# Photodiodeboard.net
KiCad netlist of a schematic drawn in Altium Designer
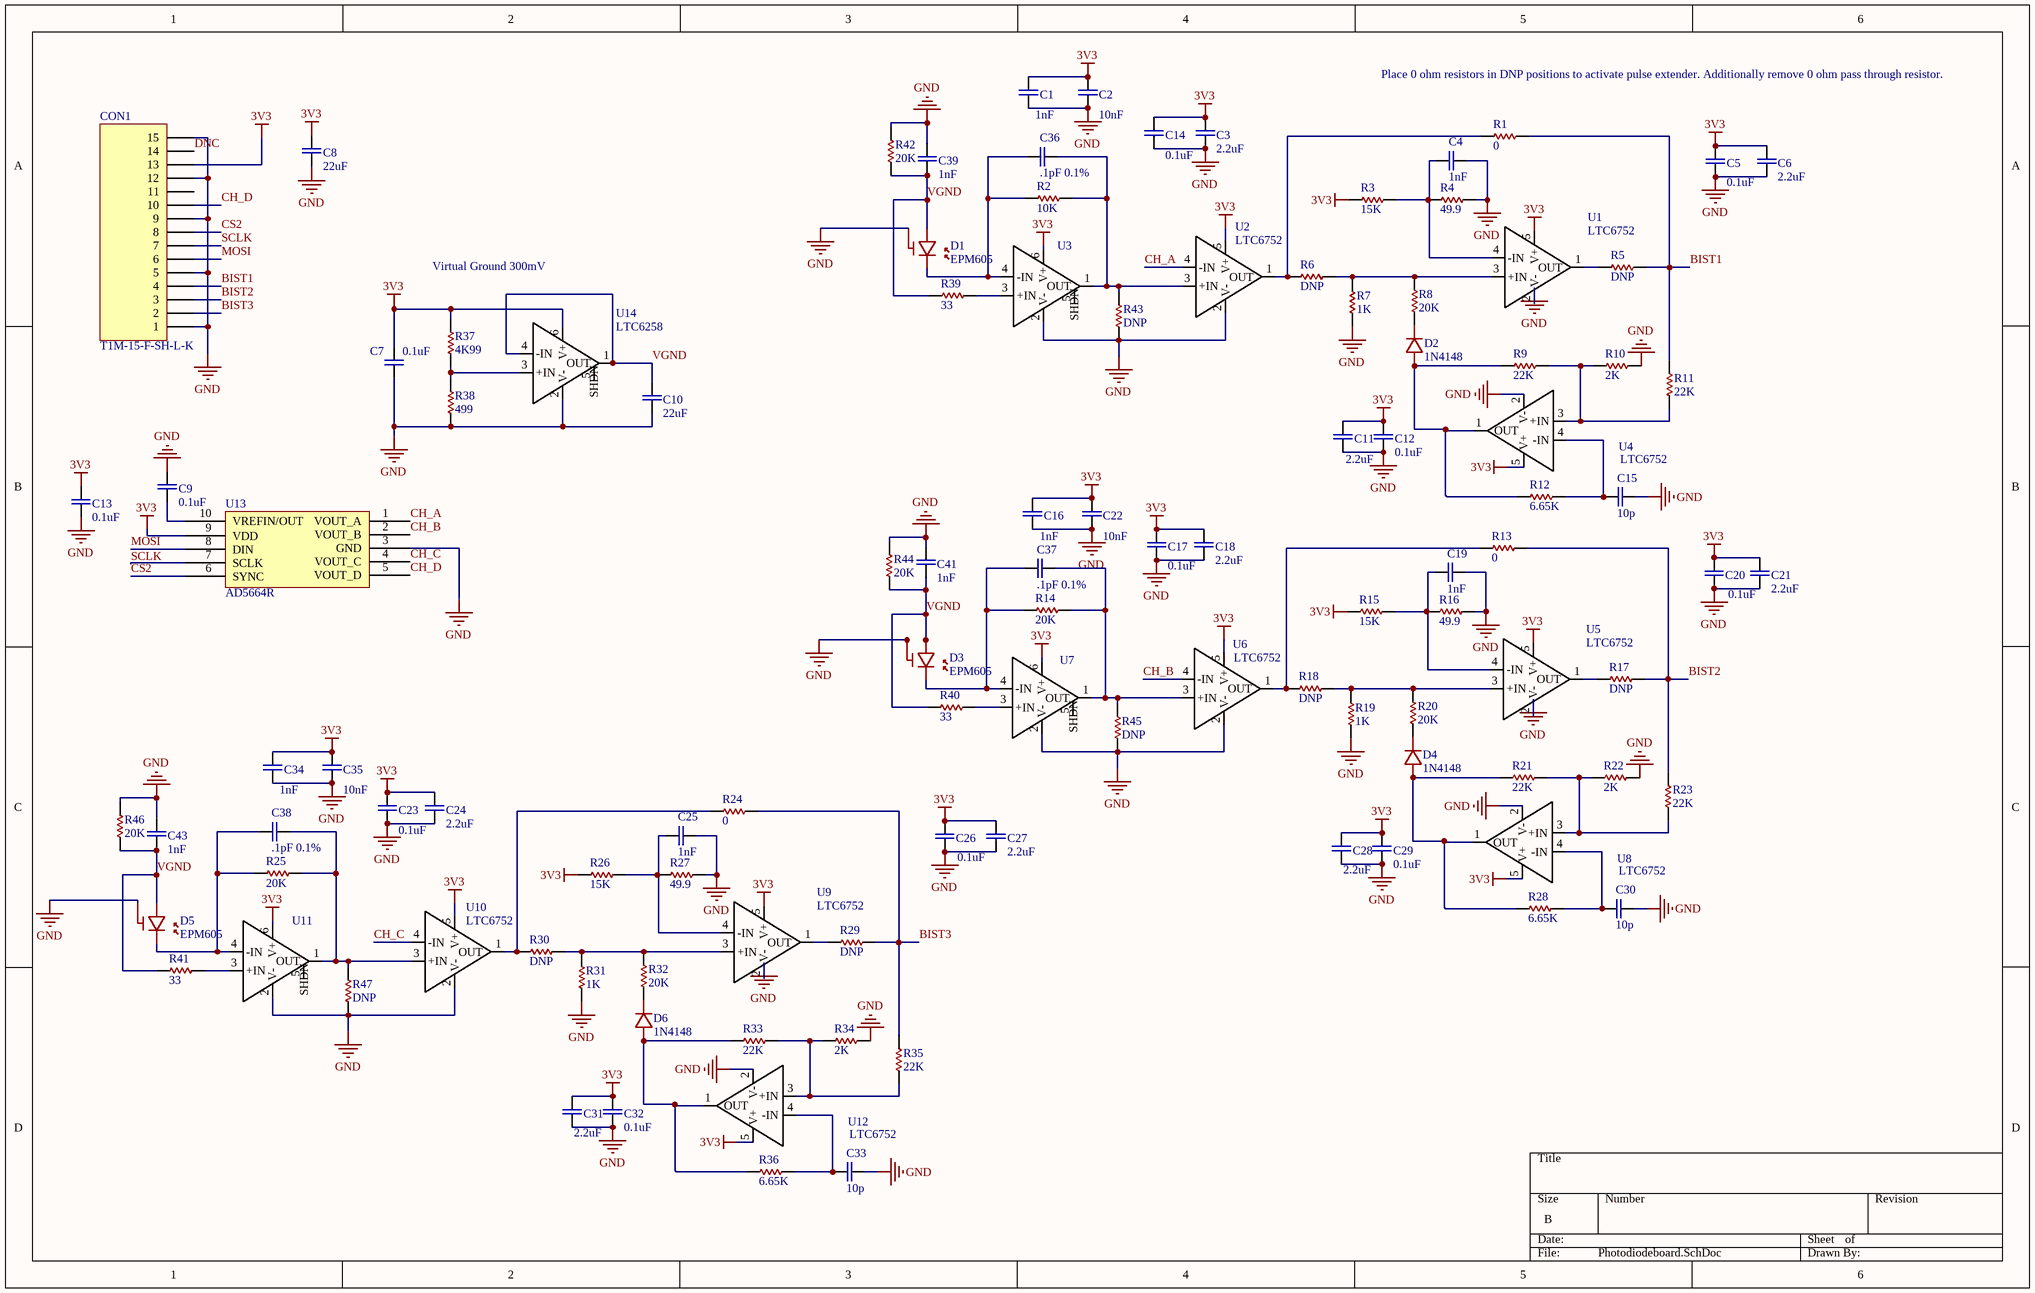
[diagram p0: Photodiodeboard.SchDoc]

(export (version "E")
  (design (tool "Eeschema 10.0.6"))
  (components
    (comp (ref "C1") (value "1nF") (footprint "0402") (libsource (lib "SchLib819") (part "Cap 0402")))
    (comp (ref "C2") (value "10nF") (footprint "0402") (libsource (lib "SchLib819") (part "Cap 0402")))
    (comp (ref "C3") (value "2.2uF") (footprint "0402") (libsource (lib "SchLib819") (part "Cap 0402")))
    (comp (ref "C4") (value "1nF") (footprint "0402") (libsource (lib "SchLib819") (part "Cap 0402")))
    (comp (ref "C5") (value "0.1uF") (footprint "0402") (libsource (lib "SchLib819") (part "Cap 0402")))
    (comp (ref "C6") (value "2.2uF") (footprint "0402") (libsource (lib "SchLib819") (part "Cap 0402")))
    (comp (ref "C7") (value "0.1uF") (footprint "0402") (libsource (lib "SchLib819") (part "Cap 0402")))
    (comp (ref "C8") (value "22uF") (footprint "0603") (libsource (lib "SchLib819") (part "Cap 0603")))
    (comp (ref "C9") (value "0.1uF") (footprint "0402") (libsource (lib "SchLib819") (part "Cap 0402")))
    (comp (ref "C10") (value "22uF") (footprint "0603") (libsource (lib "SchLib819") (part "Cap 0603")))
    (comp (ref "C11") (value "2.2uF") (footprint "0402") (libsource (lib "SchLib819") (part "Cap 0402")))
    (comp (ref "C12") (value "0.1uF") (footprint "0402") (libsource (lib "SchLib819") (part "Cap 0402")))
    (comp (ref "C13") (value "0.1uF") (footprint "0402") (libsource (lib "SchLib819") (part "Cap 0402")))
    (comp (ref "C14") (value "0.1uF") (footprint "0402") (libsource (lib "SchLib819") (part "Cap 0402")))
    (comp (ref "C15") (value "10p") (footprint "0402") (libsource (lib "SchLib819") (part "Cap 0402")))
    (comp (ref "C16") (value "1nF") (footprint "0402") (libsource (lib "SchLib819") (part "Cap 0402")))
    (comp (ref "C17") (value "0.1uF") (footprint "0402") (libsource (lib "SchLib819") (part "Cap 0402")))
    (comp (ref "C18") (value "2.2uF") (footprint "0402") (libsource (lib "SchLib819") (part "Cap 0402")))
    (comp (ref "C19") (value "1nF") (footprint "0402") (libsource (lib "SchLib819") (part "Cap 0402")))
    (comp (ref "C20") (value "0.1uF") (footprint "0402") (libsource (lib "SchLib819") (part "Cap 0402")))
    (comp (ref "C21") (value "2.2uF") (footprint "0402") (libsource (lib "SchLib819") (part "Cap 0402")))
    (comp (ref "C22") (value "10nF") (footprint "0402") (libsource (lib "SchLib819") (part "Cap 0402")))
    (comp (ref "C23") (value "0.1uF") (footprint "0402") (libsource (lib "SchLib819") (part "Cap 0402")))
    (comp (ref "C24") (value "2.2uF") (footprint "0402") (libsource (lib "SchLib819") (part "Cap 0402")))
    (comp (ref "C25") (value "1nF") (footprint "0402") (libsource (lib "SchLib819") (part "Cap 0402")))
    (comp (ref "C26") (value "0.1uF") (footprint "0402") (libsource (lib "SchLib819") (part "Cap 0402")))
    (comp (ref "C27") (value "2.2uF") (footprint "0402") (libsource (lib "SchLib819") (part "Cap 0402")))
    (comp (ref "C28") (value "2.2uF") (footprint "0402") (libsource (lib "SchLib819") (part "Cap 0402")))
    (comp (ref "C29") (value "0.1uF") (footprint "0402") (libsource (lib "SchLib819") (part "Cap 0402")))
    (comp (ref "C30") (value "10p") (footprint "0402") (libsource (lib "SchLib819") (part "Cap 0402")))
    (comp (ref "C31") (value "2.2uF") (footprint "0402") (libsource (lib "SchLib819") (part "Cap 0402")))
    (comp (ref "C32") (value "0.1uF") (footprint "0402") (libsource (lib "SchLib819") (part "Cap 0402")))
    (comp (ref "C33") (value "10p") (footprint "0402") (libsource (lib "SchLib819") (part "Cap 0402")))
    (comp (ref "C34") (value "1nF") (footprint "0402") (libsource (lib "SchLib819") (part "Cap 0402")))
    (comp (ref "C35") (value "10nF") (footprint "0402") (libsource (lib "SchLib819") (part "Cap 0402")))
    (comp (ref "C36") (value ".1pF 0.1%") (footprint "0402") (libsource (lib "SchLib819") (part "Cap 0402")))
    (comp (ref "C37") (value ".1pF 0.1%") (footprint "0402") (libsource (lib "SchLib819") (part "Cap 0402")))
    (comp (ref "C38")
      (value ".1pF 0.1%")
      (footprint "0402")
      (description ".1pF")
      (libsource (lib "SchLib819") (part "Cap 0402"))
    )
    (comp (ref "C39") (value "1nF") (footprint "0402") (libsource (lib "SchLib819") (part "Cap 0402")))
    (comp (ref "C41") (value "1nF") (footprint "0402") (libsource (lib "SchLib819") (part "Cap 0402")))
    (comp (ref "C43") (value "1nF") (footprint "0402") (libsource (lib "SchLib819") (part "Cap 0402")))
    (comp (ref "CON1")
      (value "T1M-15-F-SH-L-K")
      (footprint "T1M-15-F-SH-L-K")
      (libsource (lib "SchLib819") (part "T1M-15-F-SH-L-K"))
    )
    (comp (ref "D1") (value "EPM605") (footprint "EPM605") (libsource (lib "SchLib819") (part "EPM605")))
    (comp (ref "D2")
      (value "1N4148")
      (footprint "SOD123FL")
      (description "Fast switching diode SMD")
      (libsource (lib "SchLib819") (part "1N4148"))
    )
    (comp (ref "D3") (value "EPM605") (footprint "EPM605") (libsource (lib "SchLib819") (part "EPM605")))
    (comp (ref "D4")
      (value "1N4148")
      (footprint "SOD123FL")
      (description "Fast switching diode SMD")
      (libsource (lib "SchLib819") (part "1N4148"))
    )
    (comp (ref "D5") (value "EPM605") (footprint "EPM605") (libsource (lib "SchLib819") (part "EPM605")))
    (comp (ref "D6")
      (value "1N4148")
      (footprint "SOD123FL")
      (description "Fast switching diode SMD")
      (libsource (lib "SchLib819") (part "1N4148"))
    )
    (comp (ref "R1") (value "0") (footprint "0402") (libsource (lib "SchLib819") (part "Res 0402")))
    (comp (ref "R2") (value "10K") (footprint "0402") (libsource (lib "SchLib819") (part "Res 0402")))
    (comp (ref "R3") (value "15K") (footprint "0402") (libsource (lib "SchLib819") (part "Res 0402")))
    (comp (ref "R4") (value "49.9") (footprint "0402") (libsource (lib "SchLib819") (part "Res 0402")))
    (comp (ref "R5")
      (value "DNP")
      (footprint "0402")
      (description "0 ohm")
      (libsource (lib "SchLib819") (part "Res 0402"))
    )
    (comp (ref "R6")
      (value "DNP")
      (footprint "0402")
      (description "0 ohm")
      (libsource (lib "SchLib819") (part "Res 0402"))
    )
    (comp (ref "R7") (value "1K") (footprint "0402") (libsource (lib "SchLib819") (part "Res 0402")))
    (comp (ref "R8") (value "20K") (footprint "0402") (libsource (lib "SchLib819") (part "Res 0402")))
    (comp (ref "R9") (value "22K") (footprint "0402") (libsource (lib "SchLib819") (part "Res 0402")))
    (comp (ref "R10") (value "2K") (footprint "0402") (libsource (lib "SchLib819") (part "Res 0402")))
    (comp (ref "R11") (value "22K") (footprint "0402") (libsource (lib "SchLib819") (part "Res 0402")))
    (comp (ref "R12") (value "6.65K") (footprint "0402") (libsource (lib "SchLib819") (part "Res 0402")))
    (comp (ref "R13") (value "0") (footprint "0402") (libsource (lib "SchLib819") (part "Res 0402")))
    (comp (ref "R14") (value "20K") (footprint "0402") (libsource (lib "SchLib819") (part "Res 0402")))
    (comp (ref "R15") (value "15K") (footprint "0402") (libsource (lib "SchLib819") (part "Res 0402")))
    (comp (ref "R16") (value "49.9") (footprint "0402") (libsource (lib "SchLib819") (part "Res 0402")))
    (comp (ref "R17")
      (value "DNP")
      (footprint "0402")
      (description "0 ohm")
      (libsource (lib "SchLib819") (part "Res 0402"))
    )
    (comp (ref "R18")
      (value "DNP")
      (footprint "0402")
      (description "0 ohm")
      (libsource (lib "SchLib819") (part "Res 0402"))
    )
    (comp (ref "R19") (value "1K") (footprint "0402") (libsource (lib "SchLib819") (part "Res 0402")))
    (comp (ref "R20") (value "20K") (footprint "0402") (libsource (lib "SchLib819") (part "Res 0402")))
    (comp (ref "R21") (value "22K") (footprint "0402") (libsource (lib "SchLib819") (part "Res 0402")))
    (comp (ref "R22") (value "2K") (footprint "0402") (libsource (lib "SchLib819") (part "Res 0402")))
    (comp (ref "R23") (value "22K") (footprint "0402") (libsource (lib "SchLib819") (part "Res 0402")))
    (comp (ref "R24") (value "0") (footprint "0402") (libsource (lib "SchLib819") (part "Res 0402")))
    (comp (ref "R25") (value "20K") (footprint "0402") (libsource (lib "SchLib819") (part "Res 0402")))
    (comp (ref "R26") (value "15K") (footprint "0402") (libsource (lib "SchLib819") (part "Res 0402")))
    (comp (ref "R27") (value "49.9") (footprint "0402") (libsource (lib "SchLib819") (part "Res 0402")))
    (comp (ref "R28") (value "6.65K") (footprint "0402") (libsource (lib "SchLib819") (part "Res 0402")))
    (comp (ref "R29")
      (value "DNP")
      (footprint "0402")
      (description "0 ohm")
      (libsource (lib "SchLib819") (part "Res 0402"))
    )
    (comp (ref "R30")
      (value "DNP")
      (footprint "0402")
      (description "0 ohm")
      (libsource (lib "SchLib819") (part "Res 0402"))
    )
    (comp (ref "R31") (value "1K") (footprint "0402") (libsource (lib "SchLib819") (part "Res 0402")))
    (comp (ref "R32") (value "20K") (footprint "0402") (libsource (lib "SchLib819") (part "Res 0402")))
    (comp (ref "R33") (value "22K") (footprint "0402") (libsource (lib "SchLib819") (part "Res 0402")))
    (comp (ref "R34") (value "2K") (footprint "0402") (libsource (lib "SchLib819") (part "Res 0402")))
    (comp (ref "R35") (value "22K") (footprint "0402") (libsource (lib "SchLib819") (part "Res 0402")))
    (comp (ref "R36") (value "6.65K") (footprint "0402") (libsource (lib "SchLib819") (part "Res 0402")))
    (comp (ref "R37") (value "4K99") (footprint "0402") (libsource (lib "SchLib819") (part "Res 0402")))
    (comp (ref "R38") (value "499") (footprint "0402") (libsource (lib "SchLib819") (part "Res 0402")))
    (comp (ref "R39")
      (value "33")
      (footprint "0402")
      (description "33 ohm")
      (libsource (lib "SchLib819") (part "Res 0402"))
    )
    (comp (ref "R40")
      (value "33")
      (footprint "0402")
      (description "33 ohm")
      (libsource (lib "SchLib819") (part "Res 0402"))
    )
    (comp (ref "R41")
      (value "33")
      (footprint "0402")
      (description "33 ohm")
      (libsource (lib "SchLib819") (part "Res 0402"))
    )
    (comp (ref "R42") (value "20K") (footprint "0402") (libsource (lib "SchLib819") (part "Res 0402")))
    (comp (ref "R43")
      (value "DNP")
      (footprint "0402")
      (description "50 ohm")
      (libsource (lib "SchLib819") (part "Res 0402"))
    )
    (comp (ref "R44") (value "20K") (footprint "0402") (libsource (lib "SchLib819") (part "Res 0402")))
    (comp (ref "R45")
      (value "DNP")
      (footprint "0402")
      (description "50 ohm")
      (libsource (lib "SchLib819") (part "Res 0402"))
    )
    (comp (ref "R46") (value "20K") (footprint "0402") (libsource (lib "SchLib819") (part "Res 0402")))
    (comp (ref "R47")
      (value "DNP")
      (footprint "0402")
      (description "50 ohm")
      (libsource (lib "SchLib819") (part "Res 0402"))
    )
    (comp (ref "U1")
      (value "LTC6752")
      (footprint "TSOT-23 5 Lead")
      (libsource (lib "SchLib819") (part "LTC6752"))
    )
    (comp (ref "U2")
      (value "LTC6752")
      (footprint "TSOT-23 5 Lead")
      (libsource (lib "SchLib819") (part "LTC6752"))
    )
    (comp (ref "U3")
      (value "LTC6268-10")
      (footprint "TSOT-23 6 Lead")
      (libsource (lib "SchLib819") (part "LTC6268-10"))
    )
    (comp (ref "U4")
      (value "LTC6752")
      (footprint "TSOT-23 5 Lead")
      (libsource (lib "SchLib819") (part "LTC6752"))
    )
    (comp (ref "U5")
      (value "LTC6752")
      (footprint "TSOT-23 5 Lead")
      (libsource (lib "SchLib819") (part "LTC6752"))
    )
    (comp (ref "U6")
      (value "LTC6752")
      (footprint "TSOT-23 5 Lead")
      (libsource (lib "SchLib819") (part "LTC6752"))
    )
    (comp (ref "U7")
      (value "LTC6268-10")
      (footprint "TSOT-23 6 Lead")
      (libsource (lib "SchLib819") (part "LTC6268-10"))
    )
    (comp (ref "U8")
      (value "LTC6752")
      (footprint "TSOT-23 5 Lead")
      (libsource (lib "SchLib819") (part "LTC6752"))
    )
    (comp (ref "U9")
      (value "LTC6752")
      (footprint "TSOT-23 5 Lead")
      (libsource (lib "SchLib819") (part "LTC6752"))
    )
    (comp (ref "U10")
      (value "LTC6752")
      (footprint "TSOT-23 5 Lead")
      (libsource (lib "SchLib819") (part "LTC6752"))
    )
    (comp (ref "U11")
      (value "LTC6268-10")
      (footprint "TSOT-23 6 Lead")
      (libsource (lib "SchLib819") (part "LTC6268-10"))
    )
    (comp (ref "U12")
      (value "LTC6752")
      (footprint "TSOT-23 5 Lead")
      (libsource (lib "SchLib819") (part "LTC6752"))
    )
    (comp (ref "U13") (value "AD5664R") (footprint "MSOP-10") (libsource (lib "SchLib819") (part "AD5664R")))
    (comp (ref "U14")
      (value "LTC6258")
      (footprint "TSOT-23 6 Lead")
      (libsource (lib "SchLib819") (part "LTC6258"))
    )
  )
  (nets
    (net (code "1") (name "/BIST1") (class "Default")
      (node (ref "CON1") (pin "4") (pinfunction "4_4") (pintype "passive"))
      (node (ref "R1") (pin "1") (pintype "passive"))
      (node (ref "R11") (pin "1") (pintype "passive"))
      (node (ref "R5") (pin "1") (pintype "passive"))
    )
    (net (code "2") (name "/BIST2") (class "Default")
      (node (ref "CON1") (pin "3") (pinfunction "3_3") (pintype "passive"))
      (node (ref "R13") (pin "1") (pintype "passive"))
      (node (ref "R17") (pin "1") (pintype "passive"))
      (node (ref "R23") (pin "1") (pintype "passive"))
    )
    (net (code "3") (name "/BIST3") (class "Default")
      (node (ref "CON1") (pin "2") (pinfunction "2_2") (pintype "passive"))
      (node (ref "R24") (pin "1") (pintype "passive"))
      (node (ref "R29") (pin "1") (pintype "passive"))
      (node (ref "R35") (pin "1") (pintype "passive"))
    )
    (net (code "4") (name "/CH_A") (class "Default")
      (node (ref "U13") (pin "1") (pinfunction "VOUT_A_1") (pintype "passive"))
      (node (ref "U2") (pin "4") (pinfunction "-IN_4") (pintype "passive"))
    )
    (net (code "5") (name "/CH_B") (class "Default")
      (node (ref "U13") (pin "2") (pinfunction "VOUT_B_2") (pintype "passive"))
      (node (ref "U6") (pin "4") (pinfunction "-IN_4") (pintype "passive"))
    )
    (net (code "6") (name "/CH_C") (class "Default")
      (node (ref "U10") (pin "4") (pinfunction "-IN_4") (pintype "passive"))
      (node (ref "U13") (pin "4") (pinfunction "VOUT_C_4") (pintype "passive"))
    )
    (net (code "7") (name "/CH_D") (class "Default")
      (node (ref "CON1") (pin "10") (pinfunction "10_10") (pintype "passive"))
      (node (ref "U13") (pin "5") (pinfunction "VOUT_D_5") (pintype "passive"))
    )
    (net (code "8") (name "/CS2") (class "Default")
      (node (ref "CON1") (pin "8") (pinfunction "8_8") (pintype "passive"))
      (node (ref "U13") (pin "6") (pinfunction "SYNC_6") (pintype "passive"))
    )
    (net (code "9") (name "/DNC") (class "Default")
      (node (ref "CON1") (pin "14") (pinfunction "14_14") (pintype "passive"))
    )
    (net (code "10") (name "/MOSI") (class "Default")
      (node (ref "CON1") (pin "6") (pinfunction "6_6") (pintype "passive"))
      (node (ref "U13") (pin "8") (pinfunction "DIN_8") (pintype "passive"))
    )
    (net (code "11") (name "/SCLK") (class "Default")
      (node (ref "CON1") (pin "7") (pinfunction "7_7") (pintype "passive"))
      (node (ref "U13") (pin "7") (pinfunction "SCLK_7") (pintype "passive"))
    )
    (net (code "12") (name "/VGND") (class "Default")
      (node (ref "C10") (pin "1") (pinfunction "1_1") (pintype "passive"))
      (node (ref "C39") (pin "1") (pinfunction "1_1") (pintype "passive"))
      (node (ref "C41") (pin "1") (pinfunction "1_1") (pintype "passive"))
      (node (ref "C43") (pin "1") (pinfunction "1_1") (pintype "passive"))
      (node (ref "D1") (pin "1") (pintype "passive"))
      (node (ref "D3") (pin "1") (pintype "passive"))
      (node (ref "D5") (pin "1") (pintype "passive"))
      (node (ref "R39") (pin "2") (pintype "passive"))
      (node (ref "R40") (pin "2") (pintype "passive"))
      (node (ref "R41") (pin "2") (pintype "passive"))
      (node (ref "R42") (pin "1") (pintype "passive"))
      (node (ref "R44") (pin "1") (pintype "passive"))
      (node (ref "R46") (pin "1") (pintype "passive"))
      (node (ref "U14") (pin "1") (pinfunction "OUT_1") (pintype "passive"))
      (node (ref "U14") (pin "4") (pinfunction "-IN_4") (pintype "passive"))
    )
    (net (code "13") (name "3V3") (class "Default")
      (node (ref "C1") (pin "1") (pinfunction "1_1") (pintype "passive"))
      (node (ref "C11") (pin "1") (pinfunction "1_1") (pintype "passive"))
      (node (ref "C12") (pin "1") (pinfunction "1_1") (pintype "passive"))
      (node (ref "C13") (pin "2") (pinfunction "2_2") (pintype "passive"))
      (node (ref "C14") (pin "1") (pinfunction "1_1") (pintype "passive"))
      (node (ref "C16") (pin "1") (pinfunction "1_1") (pintype "passive"))
      (node (ref "C17") (pin "1") (pinfunction "1_1") (pintype "passive"))
      (node (ref "C18") (pin "1") (pinfunction "1_1") (pintype "passive"))
      (node (ref "C2") (pin "1") (pinfunction "1_1") (pintype "passive"))
      (node (ref "C20") (pin "1") (pinfunction "1_1") (pintype "passive"))
      (node (ref "C21") (pin "1") (pinfunction "1_1") (pintype "passive"))
      (node (ref "C22") (pin "1") (pinfunction "1_1") (pintype "passive"))
      (node (ref "C23") (pin "1") (pinfunction "1_1") (pintype "passive"))
      (node (ref "C24") (pin "1") (pinfunction "1_1") (pintype "passive"))
      (node (ref "C26") (pin "1") (pinfunction "1_1") (pintype "passive"))
      (node (ref "C27") (pin "1") (pinfunction "1_1") (pintype "passive"))
      (node (ref "C28") (pin "1") (pinfunction "1_1") (pintype "passive"))
      (node (ref "C29") (pin "1") (pinfunction "1_1") (pintype "passive"))
      (node (ref "C3") (pin "1") (pinfunction "1_1") (pintype "passive"))
      (node (ref "C31") (pin "1") (pinfunction "1_1") (pintype "passive"))
      (node (ref "C32") (pin "1") (pinfunction "1_1") (pintype "passive"))
      (node (ref "C34") (pin "1") (pinfunction "1_1") (pintype "passive"))
      (node (ref "C35") (pin "1") (pinfunction "1_1") (pintype "passive"))
      (node (ref "C5") (pin "1") (pinfunction "1_1") (pintype "passive"))
      (node (ref "C6") (pin "1") (pinfunction "1_1") (pintype "passive"))
      (node (ref "C7") (pin "2") (pinfunction "2_2") (pintype "passive"))
      (node (ref "C8") (pin "1") (pinfunction "1_1") (pintype "passive"))
      (node (ref "CON1") (pin "13") (pinfunction "13_13") (pintype "passive"))
      (node (ref "R15") (pin "2") (pintype "passive"))
      (node (ref "R26") (pin "2") (pintype "passive"))
      (node (ref "R3") (pin "2") (pintype "passive"))
      (node (ref "R37") (pin "1") (pintype "passive"))
      (node (ref "U1") (pin "5") (pinfunction "V+_5") (pintype "passive"))
      (node (ref "U10") (pin "5") (pinfunction "V+_5") (pintype "passive"))
      (node (ref "U11") (pin "6") (pinfunction "V+_6") (pintype "passive"))
      (node (ref "U12") (pin "5") (pinfunction "V+_5") (pintype "passive"))
      (node (ref "U13") (pin "9") (pinfunction "VDD_9") (pintype "passive"))
      (node (ref "U14") (pin "6") (pinfunction "V+_6") (pintype "passive"))
      (node (ref "U2") (pin "5") (pinfunction "V+_5") (pintype "passive"))
      (node (ref "U3") (pin "6") (pinfunction "V+_6") (pintype "passive"))
      (node (ref "U4") (pin "5") (pinfunction "V+_5") (pintype "passive"))
      (node (ref "U5") (pin "5") (pinfunction "V+_5") (pintype "passive"))
      (node (ref "U6") (pin "5") (pinfunction "V+_5") (pintype "passive"))
      (node (ref "U7") (pin "6") (pinfunction "V+_6") (pintype "passive"))
      (node (ref "U8") (pin "5") (pinfunction "V+_5") (pintype "passive"))
      (node (ref "U9") (pin "5") (pinfunction "V+_5") (pintype "passive"))
    )
    (net (code "14") (name "GND") (class "Default")
      (node (ref "C1") (pin "2") (pinfunction "2_2") (pintype "passive"))
      (node (ref "C10") (pin "2") (pinfunction "2_2") (pintype "passive"))
      (node (ref "C11") (pin "2") (pinfunction "2_2") (pintype "passive"))
      (node (ref "C12") (pin "2") (pinfunction "2_2") (pintype "passive"))
      (node (ref "C13") (pin "1") (pinfunction "1_1") (pintype "passive"))
      (node (ref "C14") (pin "2") (pinfunction "2_2") (pintype "passive"))
      (node (ref "C15") (pin "1") (pinfunction "1_1") (pintype "passive"))
      (node (ref "C16") (pin "2") (pinfunction "2_2") (pintype "passive"))
      (node (ref "C17") (pin "2") (pinfunction "2_2") (pintype "passive"))
      (node (ref "C18") (pin "2") (pinfunction "2_2") (pintype "passive"))
      (node (ref "C19") (pin "2") (pinfunction "2_2") (pintype "passive"))
      (node (ref "C2") (pin "2") (pinfunction "2_2") (pintype "passive"))
      (node (ref "C20") (pin "2") (pinfunction "2_2") (pintype "passive"))
      (node (ref "C21") (pin "2") (pinfunction "2_2") (pintype "passive"))
      (node (ref "C22") (pin "2") (pinfunction "2_2") (pintype "passive"))
      (node (ref "C23") (pin "2") (pinfunction "2_2") (pintype "passive"))
      (node (ref "C24") (pin "2") (pinfunction "2_2") (pintype "passive"))
      (node (ref "C25") (pin "2") (pinfunction "2_2") (pintype "passive"))
      (node (ref "C26") (pin "2") (pinfunction "2_2") (pintype "passive"))
      (node (ref "C27") (pin "2") (pinfunction "2_2") (pintype "passive"))
      (node (ref "C28") (pin "2") (pinfunction "2_2") (pintype "passive"))
      (node (ref "C29") (pin "2") (pinfunction "2_2") (pintype "passive"))
      (node (ref "C3") (pin "2") (pinfunction "2_2") (pintype "passive"))
      (node (ref "C30") (pin "1") (pinfunction "1_1") (pintype "passive"))
      (node (ref "C31") (pin "2") (pinfunction "2_2") (pintype "passive"))
      (node (ref "C32") (pin "2") (pinfunction "2_2") (pintype "passive"))
      (node (ref "C33") (pin "1") (pinfunction "1_1") (pintype "passive"))
      (node (ref "C34") (pin "2") (pinfunction "2_2") (pintype "passive"))
      (node (ref "C35") (pin "2") (pinfunction "2_2") (pintype "passive"))
      (node (ref "C39") (pin "2") (pinfunction "2_2") (pintype "passive"))
      (node (ref "C4") (pin "2") (pinfunction "2_2") (pintype "passive"))
      (node (ref "C41") (pin "2") (pinfunction "2_2") (pintype "passive"))
      (node (ref "C43") (pin "2") (pinfunction "2_2") (pintype "passive"))
      (node (ref "C5") (pin "2") (pinfunction "2_2") (pintype "passive"))
      (node (ref "C6") (pin "2") (pinfunction "2_2") (pintype "passive"))
      (node (ref "C7") (pin "1") (pinfunction "1_1") (pintype "passive"))
      (node (ref "C8") (pin "2") (pinfunction "2_2") (pintype "passive"))
      (node (ref "C9") (pin "1") (pinfunction "1_1") (pintype "passive"))
      (node (ref "CON1") (pin "1") (pinfunction "1_1") (pintype "passive"))
      (node (ref "CON1") (pin "12") (pinfunction "12_12") (pintype "passive"))
      (node (ref "CON1") (pin "15") (pinfunction "15_15") (pintype "passive"))
      (node (ref "CON1") (pin "5") (pinfunction "5_5") (pintype "passive"))
      (node (ref "CON1") (pin "9") (pinfunction "9_9") (pintype "passive"))
      (node (ref "D1") (pin "3") (pintype "passive"))
      (node (ref "D3") (pin "3") (pintype "passive"))
      (node (ref "D5") (pin "3") (pintype "passive"))
      (node (ref "R10") (pin "1") (pintype "passive"))
      (node (ref "R16") (pin "1") (pintype "passive"))
      (node (ref "R19") (pin "2") (pintype "passive"))
      (node (ref "R22") (pin "1") (pintype "passive"))
      (node (ref "R27") (pin "1") (pintype "passive"))
      (node (ref "R31") (pin "2") (pintype "passive"))
      (node (ref "R34") (pin "1") (pintype "passive"))
      (node (ref "R38") (pin "2") (pintype "passive"))
      (node (ref "R4") (pin "1") (pintype "passive"))
      (node (ref "R42") (pin "2") (pintype "passive"))
      (node (ref "R43") (pin "2") (pintype "passive"))
      (node (ref "R44") (pin "2") (pintype "passive"))
      (node (ref "R45") (pin "2") (pintype "passive"))
      (node (ref "R46") (pin "2") (pintype "passive"))
      (node (ref "R47") (pin "2") (pintype "passive"))
      (node (ref "R7") (pin "2") (pintype "passive"))
      (node (ref "U1") (pin "2") (pinfunction "V-_2") (pintype "passive"))
      (node (ref "U10") (pin "2") (pinfunction "V-_2") (pintype "passive"))
      (node (ref "U11") (pin "2") (pinfunction "V-_2") (pintype "passive"))
      (node (ref "U12") (pin "2") (pinfunction "V-_2") (pintype "passive"))
      (node (ref "U13") (pin "3") (pinfunction "GND_3") (pintype "passive"))
      (node (ref "U14") (pin "2") (pinfunction "V-_2") (pintype "passive"))
      (node (ref "U2") (pin "2") (pinfunction "V-_2") (pintype "passive"))
      (node (ref "U3") (pin "2") (pinfunction "V-_2") (pintype "passive"))
      (node (ref "U4") (pin "2") (pinfunction "V-_2") (pintype "passive"))
      (node (ref "U5") (pin "2") (pinfunction "V-_2") (pintype "passive"))
      (node (ref "U6") (pin "2") (pinfunction "V-_2") (pintype "passive"))
      (node (ref "U7") (pin "2") (pinfunction "V-_2") (pintype "passive"))
      (node (ref "U8") (pin "2") (pinfunction "V-_2") (pintype "passive"))
      (node (ref "U9") (pin "2") (pinfunction "V-_2") (pintype "passive"))
    )
    (net (code "15") (name "Net-(D2-Pad2)") (class "Default")
      (node (ref "D2") (pin "2") (pintype "passive"))
      (node (ref "R8") (pin "1") (pintype "passive"))
    )
    (net (code "16") (name "Net-(D4-Pad2)") (class "Default")
      (node (ref "D4") (pin "2") (pintype "passive"))
      (node (ref "R20") (pin "1") (pintype "passive"))
    )
    (net (code "17") (name "Net-(D6-Pad2)") (class "Default")
      (node (ref "D6") (pin "2") (pintype "passive"))
      (node (ref "R32") (pin "1") (pintype "passive"))
    )
    (net (code "18") (name "Net-(U1-+IN)") (class "Default")
      (node (ref "R6") (pin "1") (pintype "passive"))
      (node (ref "R7") (pin "1") (pintype "passive"))
      (node (ref "R8") (pin "2") (pintype "passive"))
      (node (ref "U1") (pin "3") (pinfunction "+IN_3") (pintype "passive"))
    )
    (net (code "19") (name "Net-(U1--IN)") (class "Default")
      (node (ref "C4") (pin "1") (pinfunction "1_1") (pintype "passive"))
      (node (ref "R3") (pin "1") (pintype "passive"))
      (node (ref "R4") (pin "2") (pintype "passive"))
      (node (ref "U1") (pin "4") (pinfunction "-IN_4") (pintype "passive"))
    )
    (net (code "20") (name "Net-(U1-OUT)") (class "Default")
      (node (ref "R5") (pin "2") (pintype "passive"))
      (node (ref "U1") (pin "1") (pinfunction "OUT_1") (pintype "passive"))
    )
    (net (code "21") (name "Net-(U2-+IN)") (class "Default")
      (node (ref "C36") (pin "2") (pinfunction "2_2") (pintype "passive"))
      (node (ref "R2") (pin "1") (pintype "passive"))
      (node (ref "R43") (pin "1") (pintype "passive"))
      (node (ref "U2") (pin "3") (pinfunction "+IN_3") (pintype "passive"))
      (node (ref "U3") (pin "1") (pinfunction "OUT_1") (pintype "passive"))
    )
    (net (code "22") (name "Net-(U2-OUT)") (class "Default")
      (node (ref "R1") (pin "2") (pintype "passive"))
      (node (ref "R6") (pin "2") (pintype "passive"))
      (node (ref "U2") (pin "1") (pinfunction "OUT_1") (pintype "passive"))
    )
    (net (code "23") (name "Net-(U3-+IN)") (class "Default")
      (node (ref "R39") (pin "1") (pintype "passive"))
      (node (ref "U3") (pin "3") (pinfunction "+IN_3") (pintype "passive"))
    )
    (net (code "24") (name "Net-(U3--IN)") (class "Default")
      (node (ref "C36") (pin "1") (pinfunction "1_1") (pintype "passive"))
      (node (ref "D1") (pin "2") (pintype "passive"))
      (node (ref "R2") (pin "2") (pintype "passive"))
      (node (ref "U3") (pin "4") (pinfunction "-IN_4") (pintype "passive"))
    )
    (net (code "25") (name "Net-(U4-+IN)") (class "Default")
      (node (ref "R10") (pin "2") (pintype "passive"))
      (node (ref "R11") (pin "2") (pintype "passive"))
      (node (ref "R9") (pin "1") (pintype "passive"))
      (node (ref "U4") (pin "3") (pinfunction "+IN_3") (pintype "passive"))
    )
    (net (code "26") (name "Net-(U4--IN)") (class "Default")
      (node (ref "C15") (pin "2") (pinfunction "2_2") (pintype "passive"))
      (node (ref "R12") (pin "1") (pintype "passive"))
      (node (ref "U4") (pin "4") (pinfunction "-IN_4") (pintype "passive"))
    )
    (net (code "27") (name "Net-(U4-OUT)") (class "Default")
      (node (ref "D2") (pin "1") (pintype "passive"))
      (node (ref "R12") (pin "2") (pintype "passive"))
      (node (ref "R9") (pin "2") (pintype "passive"))
      (node (ref "U4") (pin "1") (pinfunction "OUT_1") (pintype "passive"))
    )
    (net (code "28") (name "Net-(U5-+IN)") (class "Default")
      (node (ref "R18") (pin "1") (pintype "passive"))
      (node (ref "R19") (pin "1") (pintype "passive"))
      (node (ref "R20") (pin "2") (pintype "passive"))
      (node (ref "U5") (pin "3") (pinfunction "+IN_3") (pintype "passive"))
    )
    (net (code "29") (name "Net-(U5--IN)") (class "Default")
      (node (ref "C19") (pin "1") (pinfunction "1_1") (pintype "passive"))
      (node (ref "R15") (pin "1") (pintype "passive"))
      (node (ref "R16") (pin "2") (pintype "passive"))
      (node (ref "U5") (pin "4") (pinfunction "-IN_4") (pintype "passive"))
    )
    (net (code "30") (name "Net-(U5-OUT)") (class "Default")
      (node (ref "R17") (pin "2") (pintype "passive"))
      (node (ref "U5") (pin "1") (pinfunction "OUT_1") (pintype "passive"))
    )
    (net (code "31") (name "Net-(U6-+IN)") (class "Default")
      (node (ref "C37") (pin "2") (pinfunction "2_2") (pintype "passive"))
      (node (ref "R14") (pin "1") (pintype "passive"))
      (node (ref "R45") (pin "1") (pintype "passive"))
      (node (ref "U6") (pin "3") (pinfunction "+IN_3") (pintype "passive"))
      (node (ref "U7") (pin "1") (pinfunction "OUT_1") (pintype "passive"))
    )
    (net (code "32") (name "Net-(U6-OUT)") (class "Default")
      (node (ref "R13") (pin "2") (pintype "passive"))
      (node (ref "R18") (pin "2") (pintype "passive"))
      (node (ref "U6") (pin "1") (pinfunction "OUT_1") (pintype "passive"))
    )
    (net (code "33") (name "Net-(U7-+IN)") (class "Default")
      (node (ref "R40") (pin "1") (pintype "passive"))
      (node (ref "U7") (pin "3") (pinfunction "+IN_3") (pintype "passive"))
    )
    (net (code "34") (name "Net-(U7--IN)") (class "Default")
      (node (ref "C37") (pin "1") (pinfunction "1_1") (pintype "passive"))
      (node (ref "D3") (pin "2") (pintype "passive"))
      (node (ref "R14") (pin "2") (pintype "passive"))
      (node (ref "U7") (pin "4") (pinfunction "-IN_4") (pintype "passive"))
    )
    (net (code "35") (name "Net-(U8-+IN)") (class "Default")
      (node (ref "R21") (pin "1") (pintype "passive"))
      (node (ref "R22") (pin "2") (pintype "passive"))
      (node (ref "R23") (pin "2") (pintype "passive"))
      (node (ref "U8") (pin "3") (pinfunction "+IN_3") (pintype "passive"))
    )
    (net (code "36") (name "Net-(U8--IN)") (class "Default")
      (node (ref "C30") (pin "2") (pinfunction "2_2") (pintype "passive"))
      (node (ref "R28") (pin "1") (pintype "passive"))
      (node (ref "U8") (pin "4") (pinfunction "-IN_4") (pintype "passive"))
    )
    (net (code "37") (name "Net-(U8-OUT)") (class "Default")
      (node (ref "D4") (pin "1") (pintype "passive"))
      (node (ref "R21") (pin "2") (pintype "passive"))
      (node (ref "R28") (pin "2") (pintype "passive"))
      (node (ref "U8") (pin "1") (pinfunction "OUT_1") (pintype "passive"))
    )
    (net (code "38") (name "Net-(U9-+IN)") (class "Default")
      (node (ref "R30") (pin "1") (pintype "passive"))
      (node (ref "R31") (pin "1") (pintype "passive"))
      (node (ref "R32") (pin "2") (pintype "passive"))
      (node (ref "U9") (pin "3") (pinfunction "+IN_3") (pintype "passive"))
    )
    (net (code "39") (name "Net-(U9--IN)") (class "Default")
      (node (ref "C25") (pin "1") (pinfunction "1_1") (pintype "passive"))
      (node (ref "R26") (pin "1") (pintype "passive"))
      (node (ref "R27") (pin "2") (pintype "passive"))
      (node (ref "U9") (pin "4") (pinfunction "-IN_4") (pintype "passive"))
    )
    (net (code "40") (name "Net-(U9-OUT)") (class "Default")
      (node (ref "R29") (pin "2") (pintype "passive"))
      (node (ref "U9") (pin "1") (pinfunction "OUT_1") (pintype "passive"))
    )
    (net (code "41") (name "Net-(U10-+IN)") (class "Default")
      (node (ref "C38") (pin "2") (pinfunction "2_2") (pintype "passive"))
      (node (ref "R25") (pin "1") (pintype "passive"))
      (node (ref "R47") (pin "1") (pintype "passive"))
      (node (ref "U10") (pin "3") (pinfunction "+IN_3") (pintype "passive"))
      (node (ref "U11") (pin "1") (pinfunction "OUT_1") (pintype "passive"))
    )
    (net (code "42") (name "Net-(U10-OUT)") (class "Default")
      (node (ref "R24") (pin "2") (pintype "passive"))
      (node (ref "R30") (pin "2") (pintype "passive"))
      (node (ref "U10") (pin "1") (pinfunction "OUT_1") (pintype "passive"))
    )
    (net (code "43") (name "Net-(U11-+IN)") (class "Default")
      (node (ref "R41") (pin "1") (pintype "passive"))
      (node (ref "U11") (pin "3") (pinfunction "+IN_3") (pintype "passive"))
    )
    (net (code "44") (name "Net-(U11--IN)") (class "Default")
      (node (ref "C38") (pin "1") (pinfunction "1_1") (pintype "passive"))
      (node (ref "D5") (pin "2") (pintype "passive"))
      (node (ref "R25") (pin "2") (pintype "passive"))
      (node (ref "U11") (pin "4") (pinfunction "-IN_4") (pintype "passive"))
    )
    (net (code "45") (name "Net-(U12-+IN)") (class "Default")
      (node (ref "R33") (pin "1") (pintype "passive"))
      (node (ref "R34") (pin "2") (pintype "passive"))
      (node (ref "R35") (pin "2") (pintype "passive"))
      (node (ref "U12") (pin "3") (pinfunction "+IN_3") (pintype "passive"))
    )
    (net (code "46") (name "Net-(U12--IN)") (class "Default")
      (node (ref "C33") (pin "2") (pinfunction "2_2") (pintype "passive"))
      (node (ref "R36") (pin "1") (pintype "passive"))
      (node (ref "U12") (pin "4") (pinfunction "-IN_4") (pintype "passive"))
    )
    (net (code "47") (name "Net-(U12-OUT)") (class "Default")
      (node (ref "D6") (pin "1") (pintype "passive"))
      (node (ref "R33") (pin "2") (pintype "passive"))
      (node (ref "R36") (pin "2") (pintype "passive"))
      (node (ref "U12") (pin "1") (pinfunction "OUT_1") (pintype "passive"))
    )
    (net (code "48") (name "Net-(U13-VREFIN{slash}OUT)") (class "Default")
      (node (ref "C9") (pin "2") (pinfunction "2_2") (pintype "passive"))
      (node (ref "U13") (pin "10") (pinfunction "VREFIN/OUT_10") (pintype "passive"))
    )
    (net (code "49") (name "Net-(U14-+IN)") (class "Default")
      (node (ref "R37") (pin "2") (pintype "passive"))
      (node (ref "R38") (pin "1") (pintype "passive"))
      (node (ref "U14") (pin "3") (pinfunction "+IN_3") (pintype "passive"))
    )
    (net (code "50") (name "unconnected-(CON1-Pad11)") (class "Default")
      (node (ref "CON1") (pin "11") (pinfunction "11_11") (pintype "passive"))
    )
    (net (code "51") (name "unconnected-(U3-SHDN-Pad5)") (class "Default")
      (node (ref "U3") (pin "5") (pinfunction "SHDN_5") (pintype "passive"))
    )
    (net (code "52") (name "unconnected-(U7-SHDN-Pad5)") (class "Default")
      (node (ref "U7") (pin "5") (pinfunction "SHDN_5") (pintype "passive"))
    )
    (net (code "53") (name "unconnected-(U11-SHDN-Pad5)") (class "Default")
      (node (ref "U11") (pin "5") (pinfunction "SHDN_5") (pintype "passive"))
    )
    (net (code "54") (name "unconnected-(U14-SHDN-Pad5)") (class "Default")
      (node (ref "U14") (pin "5") (pinfunction "SHDN_5") (pintype "passive"))
    )
  )
)
